# USB-C_PD.net
KiCad netlist of a schematic drawn in Altium Designer
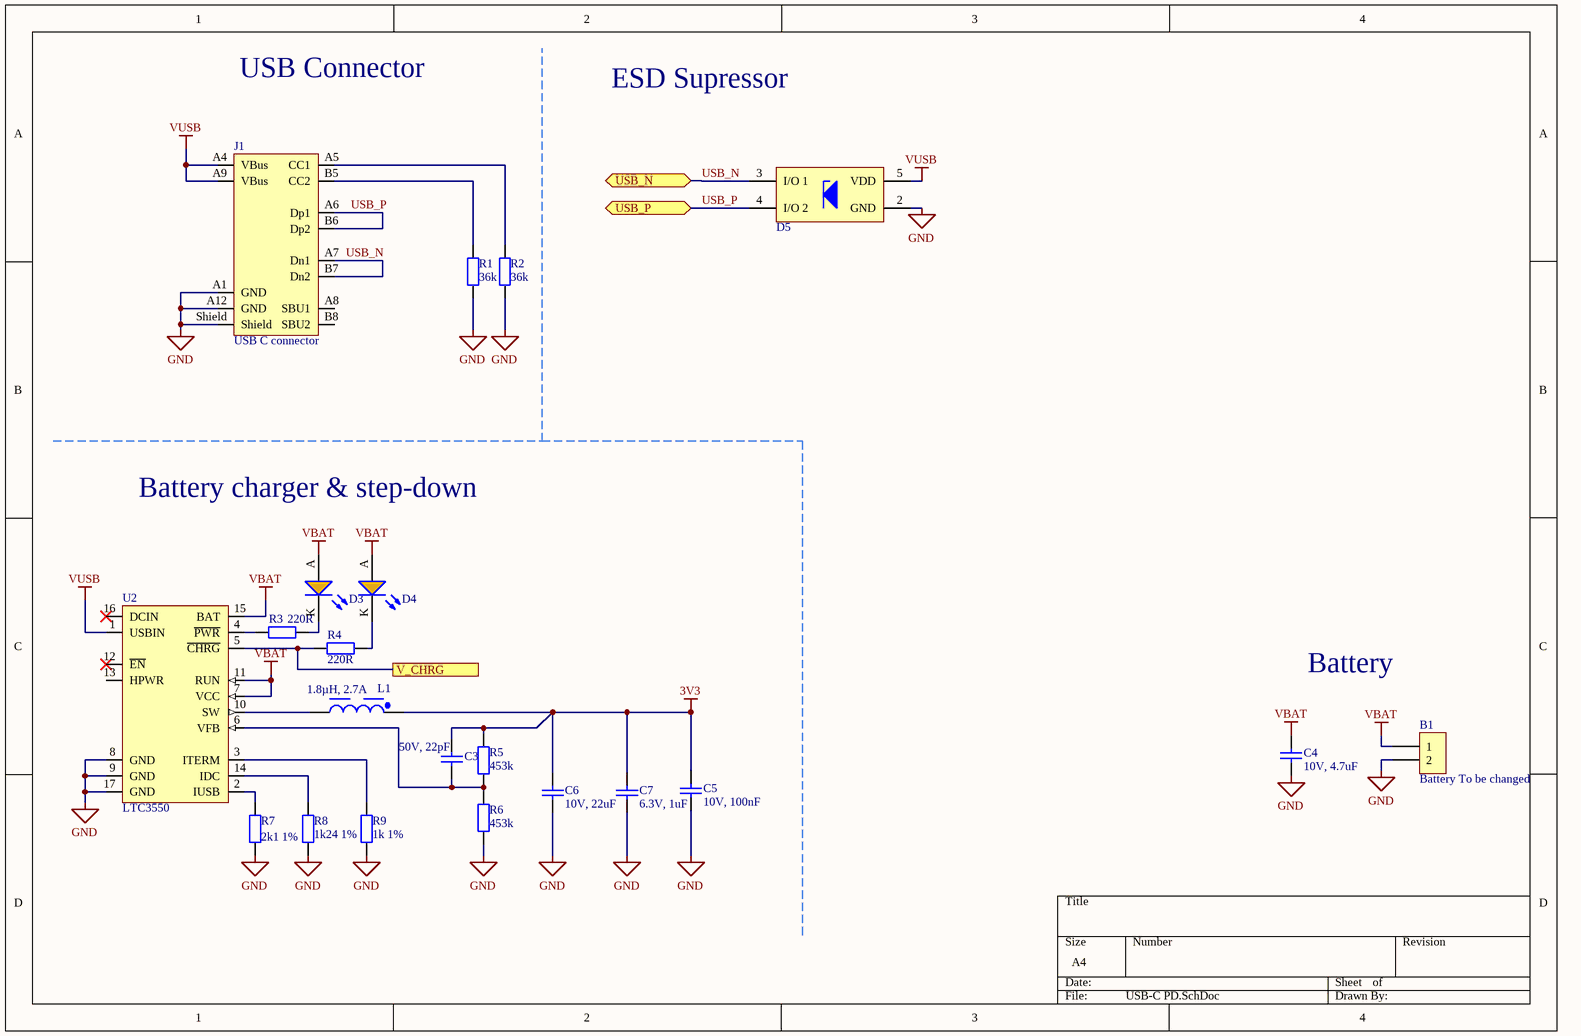
[diagram p0: USB-C PD.SchDoc]

(export (version "E")
  (design (tool "Eeschema 10.0.6"))
  (components
    (comp (ref "B1")
      (value "Battery To be changed")
      (footprint "letev2")
      (libsource (lib "VolkD3D") (part "header2"))
    )
    (comp (ref "C3")
      (value "50V, 22pF")
      (footprint "0402_1x0.5x0.5mm")
      (description "WCAP-CSGP Ceramic Capacitors, 0402, NP0, 50V, 22pF")
      (fields (field (name "PART NUMBER") "885012005057") (field (name "PUBLISHER") "Wurth Elektronik"))
      (libsource (lib "ALTIUM-WCAP-CSGP-0603-rev17b") (part "885012005057"))
    )
    (comp (ref "C4")
      (value "10V, 4.7uF")
      (footprint "0603_1.6x0.8x0.8mm_Reflow Soldering")
      (description "WCAP-CSGP Ceramic Capacitors, 0603, X5R, 10V, 4.7uF")
      (fields (field (name "PART NUMBER") "885012106012") (field (name "PUBLISHER") "Wurth Elektronik"))
      (libsource (lib "ALTIUM-WCAP-CSGP-0603-rev17b") (part "885012106012"))
    )
    (comp (ref "C5")
      (value "10V, 100nF")
      (footprint "0603_1.6x0.8x0.8mm_Reflow Soldering")
      (description "WCAP-CSGP Ceramic Capacitors, 0603, X7R, 10V, 100nF")
      (fields (field (name "PART NUMBER") "885012206020") (field (name "PUBLISHER") "Wurth Elektronik"))
      (libsource (lib "ALTIUM-WCAP-CSGP-0603-rev17b") (part "885012206020"))
    )
    (comp (ref "C6")
      (value "10V, 22uF")
      (footprint "0805_2x1.25x1.25mm_Reflow Soldering")
      (description "WCAP-CSGP Ceramic Capacitors, 0805, X5R, 10V, 22uF")
      (fields (field (name "PART NUMBER") "885012107011") (field (name "PUBLISHER") "Wurth Elektronik"))
      (libsource (lib "ALTIUM-WCAP-CSGP-0603-rev17b") (part "885012107011"))
    )
    (comp (ref "C7")
      (value "6.3V, 1uF")
      (footprint "0603_1.6x0.8x0.8mm_Reflow Soldering")
      (description "WCAP-CSGP Ceramic Capacitors, 0603, X5R, 6.3V, 1uF")
      (fields (field (name "PART NUMBER") "885012106003") (field (name "PUBLISHER") "Wurth Elektronik"))
      (libsource (lib "ALTIUM-WCAP-CSGP-0603-rev17b") (part "885012106003"))
    )
    (comp (ref "D3")
      (value "Amber, 2V, 140°")
      (footprint "WL-SMCW_0603_150060xx75000")
      (description "WL-SMCW Mono-color Chip LED Waterclear, SMT, size 0603, Amber, 2V, 140°")
      (fields
        (field (name "MANUFACTURER PART NUMBER") "150060AS75000")
        (field (name "MANUFACTURER") "Wurth Elektronik")
      )
      (libsource (lib "Altium_WL-SMCW (rev22b)") (part "150060AS75000"))
    )
    (comp (ref "D4")
      (value "Amber, 2V, 140°")
      (footprint "WL-SMCW_0603_150060xx75000")
      (description "WL-SMCW Mono-color Chip LED Waterclear, SMT, size 0603, Amber, 2V, 140°")
      (fields
        (field (name "MANUFACTURER PART NUMBER") "150060AS75000")
        (field (name "MANUFACTURER") "Wurth Elektronik")
      )
      (libsource (lib "Altium_WL-SMCW (rev22b)") (part "150060AS75000"))
    )
    (comp (ref "D5")
      (value "5V")
      (footprint "WE-TVS_SOT23-5L")
      (description "WE-TVS TVS Diode – High Speed Series, SOT23-5L, 2+1 Channel, 5V, 2pF")
      (fields
        (field (name "MANUFACTURER PART NUMBER") "824011")
        (field (name "MANUFACTURER") "Wurth Elektronik")
      )
      (libsource (lib "Altium_WE-TVS (rev22b)") (part "824011"))
    )
    (comp (ref "J1")
      (value "USB C connector")
      (footprint "USB4105-15-A-120")
      (description "USB4105-15-A-120")
      (libsource (lib "Oblak Library") (part "USB4105-15-A-120"))
    )
    (comp (ref "L1")
      (value "1.8µH, 2.7A")
      (footprint "WE-TPC_4828")
      (description "WE-TPC SMT Tiny Power Inductor, 4828, 1.8µH, 2.7A, 25mΩ")
      (fields
        (field (name "MANUFACTURER PART NUMBER") "7440430018")
        (field (name "MANUFACTURER") "Wurth Elektronik")
      )
      (libsource (lib "WE-TPC (rev22c)") (part "7440430018"))
    )
    (comp (ref "R1")
      (value "36k")
      (footprint "Oblak Library:R0402")
      (fields (field (name "Comment") "Res2-smd"))
      (libsource (lib "VolkD3D") (part "Res2-smd"))
    )
    (comp (ref "R2")
      (value "36k")
      (footprint "Oblak Library:R0402")
      (fields (field (name "Comment") "Res2-smd"))
      (libsource (lib "VolkD3D") (part "Res2-smd"))
    )
    (comp (ref "R3") (value "220R") (footprint "R0402") (libsource (lib "Oblak Library") (part "Res 0402")))
    (comp (ref "R4") (value "220R") (footprint "R0402") (libsource (lib "Oblak Library") (part "Res 0402")))
    (comp (ref "R5")
      (value "453k")
      (footprint "Oblak Library:R0402")
      (fields (field (name "Comment") "Res2-smd"))
      (libsource (lib "VolkD3D") (part "Res2-smd"))
    )
    (comp (ref "R6")
      (value "453k")
      (footprint "Oblak Library:R0402")
      (fields (field (name "Comment") "Res2-smd"))
      (libsource (lib "VolkD3D") (part "Res2-smd"))
    )
    (comp (ref "R7")
      (value "2k1 1%")
      (footprint "Oblak Library:R0402")
      (fields (field (name "Comment") "Res2-smd"))
      (libsource (lib "VolkD3D") (part "Res2-smd"))
    )
    (comp (ref "R8")
      (value "1k24 1%")
      (footprint "Oblak Library:R0402")
      (fields (field (name "Comment") "Res2-smd"))
      (libsource (lib "VolkD3D") (part "Res2-smd"))
    )
    (comp (ref "R9")
      (value "1k 1%")
      (footprint "Oblak Library:R0402")
      (fields (field (name "Comment") "Res2-smd"))
      (libsource (lib "VolkD3D") (part "Res2-smd"))
    )
    (comp (ref "U2")
      (value "LTC3550")
      (footprint "DHC16 Linear")
      (description "Dual Input USB/AC Adapter\r\nLi-Ion Battery Charger with\r\n600mA Buck Converter")
      (libsource (lib "Oblak Library") (part "LTC3550"))
    )
  )
  (nets
    (net (code "1") (name "/USB_N") (class "Default")
      (node (ref "D5") (pin "3") (pinfunction "I/O_1_3") (pintype "passive"))
      (node (ref "J1") (pin "A7") (pinfunction "Dn1_A7") (pintype "passive"))
      (node (ref "J1") (pin "B7") (pinfunction "Dn2_B7") (pintype "passive"))
    )
    (net (code "2") (name "/USB_P") (class "Default")
      (node (ref "D5") (pin "4") (pinfunction "I/O_2_4") (pintype "passive"))
      (node (ref "J1") (pin "A6") (pinfunction "Dp1_A6") (pintype "passive"))
      (node (ref "J1") (pin "B6") (pinfunction "Dp2_B6") (pintype "passive"))
    )
    (net (code "3") (name "/V_CHRG") (class "Default")
      (node (ref "R4") (pin "2") (pinfunction "2_2") (pintype "passive"))
      (node (ref "U2") (pin "5") (pinfunction "~{CHRG}_5") (pintype "open_collector"))
    )
    (net (code "4") (name "3V3") (class "Default")
      (node (ref "C3") (pin "2") (pinfunction "2_2") (pintype "passive"))
      (node (ref "C5") (pin "2") (pinfunction "2_2") (pintype "passive"))
      (node (ref "C6") (pin "2") (pinfunction "2_2") (pintype "passive"))
      (node (ref "C7") (pin "2") (pinfunction "2_2") (pintype "passive"))
      (node (ref "L1") (pin "1") (pinfunction "1_1") (pintype "passive"))
      (node (ref "R5") (pin "2") (pinfunction "2_2") (pintype "passive"))
    )
    (net (code "5") (name "GND") (class "Default")
      (node (ref "B1") (pin "2") (pinfunction "2_2") (pintype "passive"))
      (node (ref "C4") (pin "1") (pinfunction "1_1") (pintype "passive"))
      (node (ref "C5") (pin "1") (pinfunction "1_1") (pintype "passive"))
      (node (ref "C6") (pin "1") (pinfunction "1_1") (pintype "passive"))
      (node (ref "C7") (pin "1") (pinfunction "1_1") (pintype "passive"))
      (node (ref "D5") (pin "2") (pinfunction "GND_2") (pintype "passive"))
      (node (ref "J1") (pin "A1") (pinfunction "GND_A1") (pintype "power_in"))
      (node (ref "J1") (pin "A12") (pinfunction "GND_A12") (pintype "power_in"))
      (node (ref "J1") (pin "Shield") (pinfunction "Shield_Shield") (pintype "power_in"))
      (node (ref "R1") (pin "1") (pinfunction "1_1") (pintype "passive"))
      (node (ref "R2") (pin "1") (pinfunction "1_1") (pintype "passive"))
      (node (ref "R6") (pin "1") (pinfunction "1_1") (pintype "passive"))
      (node (ref "R7") (pin "1") (pinfunction "1_1") (pintype "passive"))
      (node (ref "R8") (pin "1") (pinfunction "1_1") (pintype "passive"))
      (node (ref "R9") (pin "1") (pinfunction "1_1") (pintype "passive"))
      (node (ref "U2") (pin "17") (pinfunction "GND_17") (pintype "power_in"))
      (node (ref "U2") (pin "8") (pinfunction "GND_8") (pintype "power_in"))
      (node (ref "U2") (pin "9") (pinfunction "GND_9") (pintype "power_in"))
    )
    (net (code "6") (name "Net-(D3-PadK)") (class "Default")
      (node (ref "D3") (pin "K") (pinfunction "K_K") (pintype "passive"))
      (node (ref "R3") (pin "1") (pinfunction "1_1") (pintype "passive"))
    )
    (net (code "7") (name "Net-(D4-PadK)") (class "Default")
      (node (ref "D4") (pin "K") (pinfunction "K_K") (pintype "passive"))
      (node (ref "R4") (pin "1") (pinfunction "1_1") (pintype "passive"))
    )
    (net (code "8") (name "Net-(J1-CC1)") (class "Default")
      (node (ref "J1") (pin "A5") (pinfunction "CC1_A5") (pintype "passive"))
      (node (ref "R2") (pin "2") (pinfunction "2_2") (pintype "passive"))
    )
    (net (code "9") (name "Net-(J1-CC2)") (class "Default")
      (node (ref "J1") (pin "B5") (pinfunction "CC2_B5") (pintype "passive"))
      (node (ref "R1") (pin "2") (pinfunction "2_2") (pintype "passive"))
    )
    (net (code "10") (name "Net-(U2-IDC)") (class "Default")
      (node (ref "R8") (pin "2") (pinfunction "2_2") (pintype "passive"))
      (node (ref "U2") (pin "14") (pinfunction "IDC_14") (pintype "passive"))
    )
    (net (code "11") (name "Net-(U2-ITERM)") (class "Default")
      (node (ref "R9") (pin "2") (pinfunction "2_2") (pintype "passive"))
      (node (ref "U2") (pin "3") (pinfunction "ITERM_3") (pintype "passive"))
    )
    (net (code "12") (name "Net-(U2-IUSB)") (class "Default")
      (node (ref "R7") (pin "2") (pinfunction "2_2") (pintype "passive"))
      (node (ref "U2") (pin "2") (pinfunction "IUSB_2") (pintype "passive"))
    )
    (net (code "13") (name "Net-(U2-SW)") (class "Default")
      (node (ref "L1") (pin "2") (pinfunction "2_2") (pintype "passive"))
      (node (ref "U2") (pin "10") (pinfunction "SW_10") (pintype "output"))
    )
    (net (code "14") (name "Net-(U2-VFB)") (class "Default")
      (node (ref "C3") (pin "1") (pinfunction "1_1") (pintype "passive"))
      (node (ref "R5") (pin "1") (pinfunction "1_1") (pintype "passive"))
      (node (ref "R6") (pin "2") (pinfunction "2_2") (pintype "passive"))
      (node (ref "U2") (pin "6") (pinfunction "VFB_6") (pintype "input"))
    )
    (net (code "15") (name "Net-(U2-~{PWR})") (class "Default")
      (node (ref "R3") (pin "2") (pinfunction "2_2") (pintype "passive"))
      (node (ref "U2") (pin "4") (pinfunction "~{PWR}_4") (pintype "open_collector"))
    )
    (net (code "16") (name "VBAT") (class "Default")
      (node (ref "B1") (pin "1") (pinfunction "1_1") (pintype "passive"))
      (node (ref "C4") (pin "2") (pinfunction "2_2") (pintype "passive"))
      (node (ref "D3") (pin "A") (pinfunction "A_A") (pintype "passive"))
      (node (ref "D4") (pin "A") (pinfunction "A_A") (pintype "passive"))
      (node (ref "U2") (pin "11") (pinfunction "RUN_11") (pintype "input"))
      (node (ref "U2") (pin "15") (pinfunction "BAT_15") (pintype "passive"))
      (node (ref "U2") (pin "7") (pinfunction "VCC_7") (pintype "input"))
    )
    (net (code "17") (name "VUSB") (class "Default")
      (node (ref "D5") (pin "5") (pinfunction "VDD_5") (pintype "passive"))
      (node (ref "J1") (pin "A4") (pinfunction "VBus_A4") (pintype "power_in"))
      (node (ref "J1") (pin "A9") (pinfunction "VBus_A9") (pintype "power_in"))
      (node (ref "U2") (pin "1") (pinfunction "USBIN_1") (pintype "power_in"))
    )
    (net (code "18") (name "unconnected-(J1-SBU1-PadA8)") (class "Default")
      (node (ref "J1") (pin "A8") (pinfunction "SBU1_A8") (pintype "passive"))
    )
    (net (code "19") (name "unconnected-(J1-SBU2-PadB8)") (class "Default")
      (node (ref "J1") (pin "B8") (pinfunction "SBU2_B8") (pintype "passive"))
    )
    (net (code "20") (name "unconnected-(U2-DCIN-Pad16)") (class "Default")
      (node (ref "U2") (pin "16") (pinfunction "DCIN_16") (pintype "power_in+no_connect"))
    )
    (net (code "21") (name "unconnected-(U2-HPWR-Pad13)") (class "Default")
      (node (ref "U2") (pin "13") (pinfunction "HPWR_13") (pintype "passive"))
    )
    (net (code "22") (name "unconnected-(U2-~{EN}-Pad12)") (class "Default")
      (node (ref "U2") (pin "12") (pinfunction "~{EN}_12") (pintype "passive+no_connect"))
    )
  )
)
